# NRF52840-Beacon-V1-4.net
KiCad netlist of a schematic drawn in Altium Designer
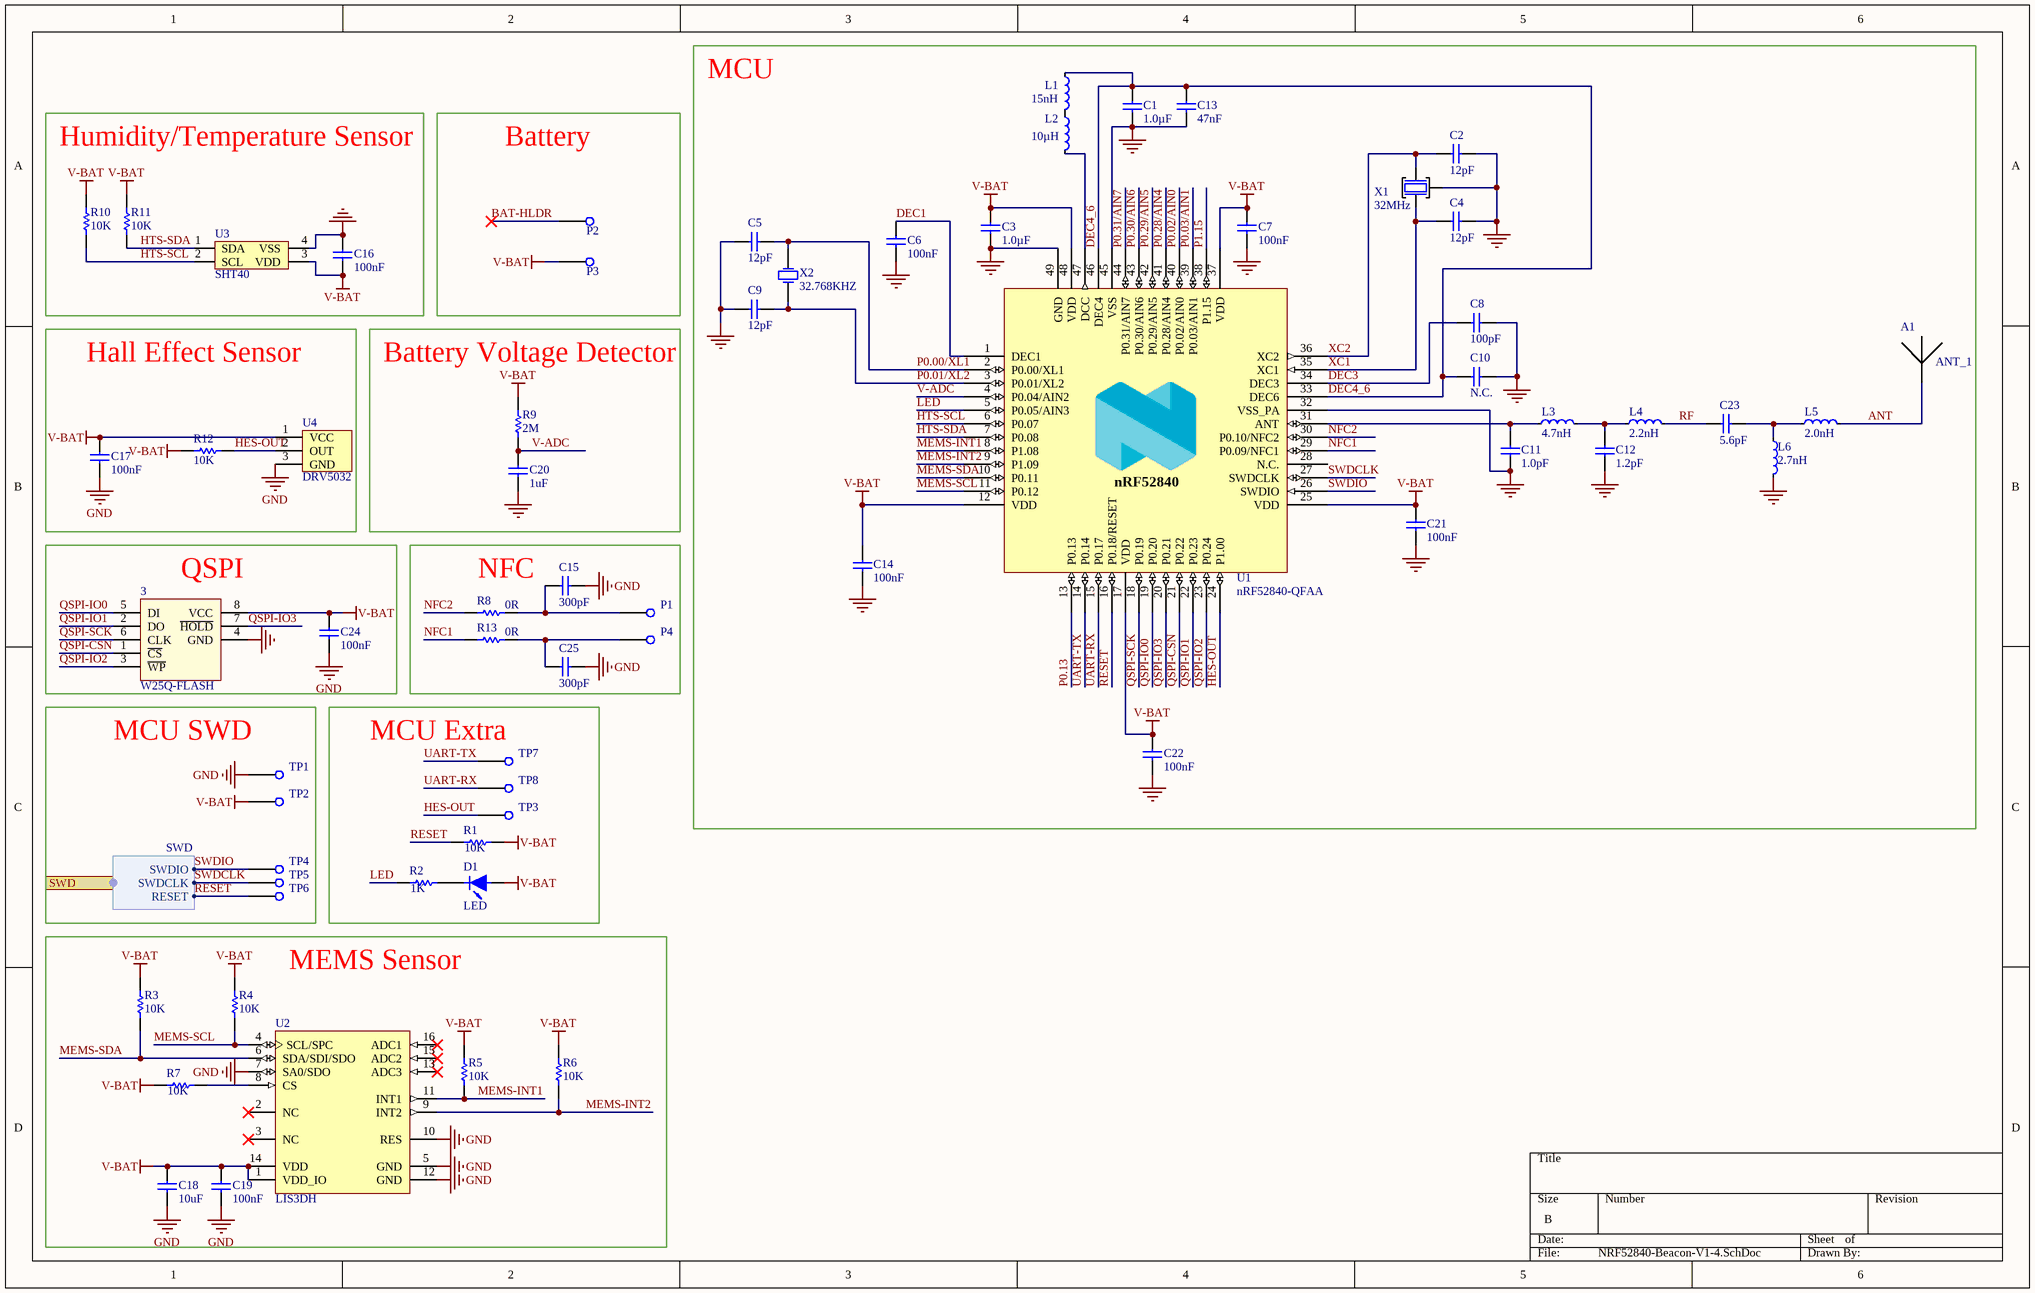
[diagram p0: NRF52840-Beacon-V1-4.SchDoc]

(export (version "E")
  (design (tool "Eeschema 10.0.6"))
  (components
    (comp (ref "3")
      (value "W25Q-FLASH")
      (footprint "SO8W_M")
      (libsource (lib "My Devices") (part "W25Q-FLASH"))
    )
    (comp (ref "A1")
      (value "ANT_1")
      (footprint "ANTENNA_2450AT18B100")
      (fields
        (field (name "PART NUMBER") "Johanson 2450AT18B100")
        (field (name "MANUFACTURER") "Johanson Technology")
        (field (name "MANUFACTURER PART NUMBER") "2450AT18B100")
        (field (name "PUBLISHER") "Nordic Semiconductor")
        (field (name "AUTHOR") "rsk")
      )
      (libsource (lib "My Devices") (part "ANT_1"))
    )
    (comp (ref "C1")
      (value "1.0µF")
      (footprint "CAPC1608N")
      (description "Capacitor, X5R, ±10%")
      (fields (field (name "PART NUMBER") "C0402-1µ0"))
      (libsource (lib "AltiumLib") (part "CAP"))
    )
    (comp (ref "C2")
      (value "12pF")
      (footprint "CAPC1608N")
      (description "Capacitor, NP0, ±2%")
      (fields (field (name "PART NUMBER") "C0201-12p"))
      (libsource (lib "AltiumLib") (part "CAP"))
    )
    (comp (ref "C3")
      (value "1.0µF")
      (footprint "CAPC1608N")
      (description "Capacitor, X5R, ±10%")
      (fields (field (name "PART NUMBER") "C0402-1µ0"))
      (libsource (lib "AltiumLib") (part "CAP"))
    )
    (comp (ref "C4")
      (value "12pF")
      (footprint "CAPC1608N")
      (description "Capacitor, NP0, ±2%")
      (fields (field (name "PART NUMBER") "C0201-12p"))
      (libsource (lib "AltiumLib") (part "CAP"))
    )
    (comp (ref "C5")
      (value "12pF")
      (footprint "CAPC1608N")
      (description "Capacitor, NP0, ±2%")
      (fields (field (name "PART NUMBER") "C0201-12p"))
      (libsource (lib "AltiumLib") (part "CAP"))
    )
    (comp (ref "C6")
      (value "100nF")
      (footprint "CAPC1608N")
      (description "Capacitor, X5R, ±10%")
      (fields (field (name "PART NUMBER") "C0201-100n"))
      (libsource (lib "AltiumLib") (part "CAP"))
    )
    (comp (ref "C7")
      (value "100nF")
      (footprint "CAPC1608N")
      (description "Capacitor, X5R, ±10%")
      (fields (field (name "PART NUMBER") "C0201-100n"))
      (libsource (lib "AltiumLib") (part "CAP"))
    )
    (comp (ref "C8")
      (value "100pF")
      (footprint "CAPC1608N")
      (description "Capacitor, NP0, ±5%")
      (fields (field (name "PART NUMBER") "C0201-100p"))
      (libsource (lib "AltiumLib") (part "CAP"))
    )
    (comp (ref "C9")
      (value "12pF")
      (footprint "CAPC1608N")
      (description "Capacitor, NP0, ±2%")
      (fields (field (name "PART NUMBER") "C0201-12p"))
      (libsource (lib "AltiumLib") (part "CAP"))
    )
    (comp (ref "C10")
      (value "N.C.")
      (footprint "CAPC1608N")
      (description "Not mounted")
      (fields (field (name "PART NUMBER") "C0201-N.C."))
      (libsource (lib "AltiumLib") (part "CAP"))
    )
    (comp (ref "C11")
      (value "1.0pF")
      (footprint "CAPC1608N")
      (description "Capacitor, NP0, ±10%")
      (fields (field (name "PART NUMBER") "C0201-1.0p"))
      (libsource (lib "AltiumLib") (part "CAP"))
    )
    (comp (ref "C12")
      (value "1.2pF")
      (footprint "CAPC1608N")
      (description "Capacitor, NP0, ±10%")
      (fields (field (name "PART NUMBER") "C0201-1.2p"))
      (libsource (lib "AltiumLib") (part "CAP"))
    )
    (comp (ref "C13")
      (value "47nF")
      (footprint "CAPC1608N")
      (description "Capacitor, X5R, ±10%")
      (fields (field (name "PART NUMBER") "C0201-47n"))
      (libsource (lib "AltiumLib") (part "CAP"))
    )
    (comp (ref "C14")
      (value "100nF")
      (footprint "CAPC1608N")
      (description "Capacitor, X5R, ±10%")
      (fields (field (name "PART NUMBER") "C0201-100n"))
      (libsource (lib "AltiumLib") (part "CAP"))
    )
    (comp (ref "C15")
      (value "300pF")
      (footprint "CAPC1608N")
      (description "Capacitor, NP0, ±2%")
      (fields (field (name "PART NUMBER") "C0201-12p"))
      (libsource (lib "AltiumLib") (part "CAP"))
    )
    (comp (ref "C16")
      (value "100nF")
      (footprint "CAPC1608N")
      (description "Capacitor, NP0, ±2%")
      (fields (field (name "PART NUMBER") "C0201-12p"))
      (libsource (lib "AltiumLib") (part "CAP"))
    )
    (comp (ref "C17")
      (value "100nF")
      (footprint "CAPC1608N")
      (description "Capacitor, NP0, ±2%")
      (fields (field (name "PART NUMBER") "C0201-12p"))
      (libsource (lib "AltiumLib") (part "CAP"))
    )
    (comp (ref "C18")
      (value "10uF")
      (footprint "CAPC1608N")
      (description "Capacitor, NP0, ±2%")
      (fields (field (name "PART NUMBER") "C0201-12p"))
      (libsource (lib "AltiumLib") (part "CAP"))
    )
    (comp (ref "C19")
      (value "100nF")
      (footprint "CAPC1608N")
      (description "Capacitor, NP0, ±2%")
      (fields (field (name "PART NUMBER") "C0201-12p"))
      (libsource (lib "AltiumLib") (part "CAP"))
    )
    (comp (ref "C20")
      (value "1uF")
      (footprint "CAPC1608N")
      (description "Capacitor, NP0, ±2%")
      (fields (field (name "PART NUMBER") "C0201-12p"))
      (libsource (lib "AltiumLib") (part "CAP"))
    )
    (comp (ref "C21")
      (value "100nF")
      (footprint "CAPC1608N")
      (description "Capacitor, X5R, ±10%")
      (fields (field (name "PART NUMBER") "C0201-100n"))
      (libsource (lib "AltiumLib") (part "CAP"))
    )
    (comp (ref "C22")
      (value "100nF")
      (footprint "CAPC1608N")
      (description "Capacitor, X5R, ±10%")
      (fields (field (name "PART NUMBER") "C0201-100n"))
      (libsource (lib "AltiumLib") (part "CAP"))
    )
    (comp (ref "C23")
      (value "5.6pF")
      (footprint "CAPC1608N")
      (description "Capacitor, NP0, ±10%")
      (fields (field (name "PART NUMBER") "C0201-1.2p"))
      (libsource (lib "AltiumLib") (part "CAP"))
    )
    (comp (ref "C24")
      (value "100nF")
      (footprint "CAPC1608N")
      (description "Capacitor, NP0, ±2%")
      (fields (field (name "PART NUMBER") "C0201-12p"))
      (libsource (lib "AltiumLib") (part "CAP"))
    )
    (comp (ref "C25")
      (value "300pF")
      (footprint "CAPC1608N")
      (description "Capacitor, NP0, ±2%")
      (fields (field (name "PART NUMBER") "C0201-12p"))
      (libsource (lib "AltiumLib") (part "CAP"))
    )
    (comp (ref "D1")
      (value "LED")
      (footprint "LED_0603")
      (fields (field (name "PUBLISHER") "Altium Limited"))
      (libsource (lib "My Devices") (part "LED"))
    )
    (comp (ref "L1")
      (value "15nH")
      (footprint "INDC1608N")
      (description "High frequency chip inductor ±10%")
      (fields (field (name "PART NUMBER") "L0402-15n"))
      (libsource (lib "AltiumLib") (part "IND"))
    )
    (comp (ref "L2")
      (value "10µH")
      (footprint "INDC1608N")
      (description "Chip inductor, IDC,min = 50 mA, ±20%")
      (fields (field (name "PART NUMBER") "L0603-10µ-TDK"))
      (libsource (lib "AltiumLib") (part "IND"))
    )
    (comp (ref "L3")
      (value "4.7nH")
      (footprint "INDC1608N")
      (description "High frequency chip inductor ±5%")
      (fields (field (name "PART NUMBER") "L0201-4n7"))
      (libsource (lib "AltiumLib") (part "IND"))
    )
    (comp (ref "L4")
      (value "2.2nH")
      (footprint "INDC1608N")
      (description "High frequency chip inductor ±5%")
      (fields (field (name "PART NUMBER") "L0201-2n2"))
      (libsource (lib "AltiumLib") (part "IND"))
    )
    (comp (ref "L5")
      (value "2.0nH")
      (footprint "INDC1608N")
      (description "High frequency chip inductor ±5%")
      (fields (field (name "PART NUMBER") "L0201-4n7"))
      (libsource (lib "AltiumLib") (part "IND"))
    )
    (comp (ref "L6")
      (value "2.7nH")
      (footprint "INDC1608N")
      (description "High frequency chip inductor ±5%")
      (fields (field (name "PART NUMBER") "L0201-4n7"))
      (libsource (lib "AltiumLib") (part "IND"))
    )
    (comp (ref "P1") (value "PIN") (footprint "PIN") (libsource (lib "My Connectors") (part "PIN")))
    (comp (ref "P2") (value "PIN") (footprint "PIN") (libsource (lib "My Connectors") (part "PIN")))
    (comp (ref "P3") (value "PIN") (footprint "PIN") (libsource (lib "My Connectors") (part "PIN")))
    (comp (ref "P4") (value "PIN") (footprint "PIN") (libsource (lib "My Connectors") (part "PIN")))
    (comp (ref "R1") (value "10K") (footprint "RESC1608N") (libsource (lib "My Devices") (part "Resistor")))
    (comp (ref "R2") (value "1K") (footprint "RESC1608N") (libsource (lib "My Devices") (part "Resistor")))
    (comp (ref "R3") (value "10K") (footprint "RESC1608N") (libsource (lib "My Devices") (part "Resistor")))
    (comp (ref "R4") (value "10K") (footprint "RESC1608N") (libsource (lib "My Devices") (part "Resistor")))
    (comp (ref "R5") (value "10K") (footprint "RESC1608N") (libsource (lib "My Devices") (part "Resistor")))
    (comp (ref "R6") (value "10K") (footprint "RESC1608N") (libsource (lib "My Devices") (part "Resistor")))
    (comp (ref "R7") (value "10K") (footprint "RESC1608N") (libsource (lib "My Devices") (part "Resistor")))
    (comp (ref "R8") (value "0R") (footprint "RESC1608N") (libsource (lib "My Devices") (part "Resistor")))
    (comp (ref "R9") (value "2M") (footprint "RESC1608N") (libsource (lib "My Devices") (part "Resistor")))
    (comp (ref "R10") (value "10K") (footprint "RESC1608N") (libsource (lib "My Devices") (part "Resistor")))
    (comp (ref "R11") (value "10K") (footprint "RESC1608N") (libsource (lib "My Devices") (part "Resistor")))
    (comp (ref "R12") (value "10K") (footprint "RESC1608N") (libsource (lib "My Devices") (part "Resistor")))
    (comp (ref "R13") (value "0R") (footprint "RESC1608N") (libsource (lib "My Devices") (part "Resistor")))
    (comp (ref "TP1") (value "PIN") (footprint "PIN") (libsource (lib "My Connectors") (part "PIN")))
    (comp (ref "TP2") (value "PIN") (footprint "PIN") (libsource (lib "My Connectors") (part "PIN")))
    (comp (ref "TP3") (value "PIN") (footprint "PIN") (libsource (lib "My Connectors") (part "PIN")))
    (comp (ref "TP4") (value "PIN") (footprint "PIN") (libsource (lib "My Connectors") (part "PIN")))
    (comp (ref "TP5") (value "PIN") (footprint "PIN") (libsource (lib "My Connectors") (part "PIN")))
    (comp (ref "TP6") (value "PIN") (footprint "PIN") (libsource (lib "My Connectors") (part "PIN")))
    (comp (ref "TP7") (value "PIN") (footprint "PIN") (libsource (lib "My Connectors") (part "PIN")))
    (comp (ref "TP8") (value "PIN") (footprint "PIN") (libsource (lib "My Connectors") (part "PIN")))
    (comp (ref "U1")
      (value "nRF52840-QFAA")
      (footprint "QFN40P600X600X90-48N")
      (description "Multi-protocol Bluetooth Low Energy, IEEE 802.15.4, ANT and 2.4GHz proprietary system-on-chip")
      (libsource (lib "AltiumLib") (part "nRF52840_QFAA"))
    )
    (comp (ref "U2")
      (value "LIS3DH")
      (footprint "LGA-16")
      (fields (field (name "MANUFACTURER") "STMicroelectronics"))
      (libsource (lib "My Devices") (part "LIS3DH"))
    )
    (comp (ref "U3")
      (value "SHT40")
      (footprint "SHT40")
      (description "High-Accuracy, Ultra-Low-Power, 16-bit, Relative Humidity and Temperature Sensor")
      (libsource (lib "My Devices") (part "SHT40"))
    )
    (comp (ref "U4")
      (value "DRV5032")
      (footprint "SOT-23")
      (description "ultra-low-power digital-switch Hall effect sensor")
      (libsource (lib "My Devices") (part "Hall_Effect_Sensor_Switch"))
    )
    (comp (ref "X1")
      (value "32MHz")
      (footprint "CRYSTAL_2016_NT")
      (description "XTAL SMD 2016, 32MHz, Cl=8pF, Total Tol: ±30ppm")
      (fields (field (name "PART NUMBER") "XTAL_SMD2016_32MHz_8pF_General_NT"))
      (libsource (lib "AltiumLib") (part "XTAL_4-pin_NT"))
    )
    (comp (ref "X2")
      (value "32.768KHZ")
      (footprint "CRYSTAL_3215")
      (libsource (lib "My Devices") (part "Crystal_Oscillator_2PIN"))
    )
  )
  (nets
    (net (code "2") (name "/ANT") (class "Default")
      (node (ref "A1") (pin "1") (pinfunction "1_1") (pintype "passive"))
      (node (ref "L5") (pin "2") (pinfunction "2_2") (pintype "passive"))
    )
    (net (code "3") (name "/BAT-HLDR") (class "Default")
      (node (ref "P2") (pin "1") (pinfunction "PIN_1") (pintype "passive+no_connect"))
    )
    (net (code "4") (name "/DEC1") (class "Default")
      (node (ref "C6") (pin "1") (pinfunction "1_1") (pintype "passive"))
      (node (ref "U1") (pin "1") (pinfunction "DEC1_1") (pintype "power_in"))
    )
    (net (code "5") (name "/DEC3") (class "Default")
      (node (ref "C8") (pin "1") (pinfunction "1_1") (pintype "passive"))
      (node (ref "U1") (pin "34") (pinfunction "DEC3_34") (pintype "power_in"))
    )
    (net (code "6") (name "/DEC4_6") (class "Default")
      (node (ref "C1") (pin "2") (pinfunction "2_2") (pintype "passive"))
      (node (ref "C10") (pin "2") (pinfunction "2_2") (pintype "passive"))
      (node (ref "C13") (pin "1") (pinfunction "1_1") (pintype "passive"))
      (node (ref "L1") (pin "1") (pinfunction "1_1") (pintype "passive"))
      (node (ref "U1") (pin "33") (pinfunction "DEC6_33") (pintype "power_in"))
      (node (ref "U1") (pin "46") (pinfunction "DEC4_46") (pintype "power_in"))
    )
    (net (code "7") (name "/HES-OUT") (class "Default")
      (node (ref "R12") (pin "2") (pinfunction "2_2") (pintype "passive"))
      (node (ref "TP3") (pin "1") (pinfunction "PIN_1") (pintype "passive"))
      (node (ref "U1") (pin "24") (pinfunction "P1.00_24") (pintype "bidirectional"))
      (node (ref "U4") (pin "2") (pinfunction "OUT_2") (pintype "passive"))
    )
    (net (code "8") (name "/HTS-SCL") (class "Default")
      (node (ref "R10") (pin "2") (pinfunction "2_2") (pintype "passive"))
      (node (ref "U1") (pin "6") (pinfunction "P0.07_6") (pintype "bidirectional"))
      (node (ref "U3") (pin "2") (pinfunction "SCL_2") (pintype "passive"))
    )
    (net (code "9") (name "/HTS-SDA") (class "Default")
      (node (ref "R11") (pin "2") (pinfunction "2_2") (pintype "passive"))
      (node (ref "U1") (pin "7") (pinfunction "P0.08_7") (pintype "bidirectional"))
      (node (ref "U3") (pin "1") (pinfunction "SDA_1") (pintype "passive"))
    )
    (net (code "10") (name "/LED") (class "Default")
      (node (ref "R2") (pin "1") (pinfunction "1_1") (pintype "passive"))
      (node (ref "U1") (pin "5") (pinfunction "P0.05/AIN3_5") (pintype "bidirectional"))
    )
    (net (code "11") (name "/MEMS-INT1") (class "Default")
      (node (ref "R5") (pin "2") (pinfunction "2_2") (pintype "passive"))
      (node (ref "U1") (pin "8") (pinfunction "P1.08_8") (pintype "bidirectional"))
      (node (ref "U2") (pin "11") (pinfunction "INT1_11") (pintype "output"))
    )
    (net (code "12") (name "/MEMS-INT2") (class "Default")
      (node (ref "R6") (pin "2") (pinfunction "2_2") (pintype "passive"))
      (node (ref "U1") (pin "9") (pinfunction "P1.09_9") (pintype "bidirectional"))
      (node (ref "U2") (pin "9") (pinfunction "INT2_9") (pintype "output"))
    )
    (net (code "13") (name "/MEMS-SCL") (class "Default")
      (node (ref "R4") (pin "2") (pinfunction "2_2") (pintype "passive"))
      (node (ref "U1") (pin "11") (pinfunction "P0.12_11") (pintype "bidirectional"))
      (node (ref "U2") (pin "4") (pinfunction "SCL/SPC_4") (pintype "bidirectional"))
    )
    (net (code "14") (name "/MEMS-SDA") (class "Default")
      (node (ref "R3") (pin "2") (pinfunction "2_2") (pintype "passive"))
      (node (ref "U1") (pin "10") (pinfunction "P0.11_10") (pintype "bidirectional"))
      (node (ref "U2") (pin "6") (pinfunction "SDA/SDI/SDO_6") (pintype "bidirectional"))
    )
    (net (code "15") (name "/NFC1") (class "Default")
      (node (ref "R13") (pin "2") (pinfunction "2_2") (pintype "passive"))
      (node (ref "U1") (pin "29") (pinfunction "P0.09/NFC1_29") (pintype "bidirectional"))
    )
    (net (code "16") (name "/NFC2") (class "Default")
      (node (ref "R8") (pin "2") (pinfunction "2_2") (pintype "passive"))
      (node (ref "U1") (pin "30") (pinfunction "P0.10/NFC2_30") (pintype "bidirectional"))
    )
    (net (code "17") (name "/P0.00{slash}XL1") (class "Default")
      (node (ref "C5") (pin "1") (pinfunction "1_1") (pintype "passive"))
      (node (ref "U1") (pin "2") (pinfunction "P0.00/XL1_2") (pintype "bidirectional"))
      (node (ref "X2") (pin "2") (pinfunction "OSC2_2") (pintype "passive"))
    )
    (net (code "18") (name "/P0.01{slash}XL2") (class "Default")
      (node (ref "C9") (pin "1") (pinfunction "1_1") (pintype "passive"))
      (node (ref "U1") (pin "3") (pinfunction "P0.01/XL2_3") (pintype "bidirectional"))
      (node (ref "X2") (pin "1") (pinfunction "OSC1_1") (pintype "passive"))
    )
    (net (code "19") (name "/P0.02{slash}AIN0") (class "Default")
      (node (ref "U1") (pin "40") (pinfunction "P0.02/AIN0_40") (pintype "bidirectional"))
    )
    (net (code "20") (name "/P0.03{slash}AIN1") (class "Default")
      (node (ref "U1") (pin "39") (pinfunction "P0.03/AIN1_39") (pintype "bidirectional"))
    )
    (net (code "21") (name "/P0.13") (class "Default")
      (node (ref "U1") (pin "13") (pinfunction "P0.13_13") (pintype "bidirectional"))
    )
    (net (code "22") (name "/P0.28{slash}AIN4") (class "Default")
      (node (ref "U1") (pin "41") (pinfunction "P0.28/AIN4_41") (pintype "bidirectional"))
    )
    (net (code "23") (name "/P0.29{slash}AIN5") (class "Default")
      (node (ref "U1") (pin "42") (pinfunction "P0.29/AIN5_42") (pintype "bidirectional"))
    )
    (net (code "24") (name "/P0.30{slash}AIN6") (class "Default")
      (node (ref "U1") (pin "43") (pinfunction "P0.30/AIN6_43") (pintype "bidirectional"))
    )
    (net (code "25") (name "/P0.31{slash}AIN7") (class "Default")
      (node (ref "U1") (pin "44") (pinfunction "P0.31/AIN7_44") (pintype "bidirectional"))
    )
    (net (code "26") (name "/P1.15") (class "Default")
      (node (ref "U1") (pin "38") (pinfunction "P1.15_38") (pintype "bidirectional"))
    )
    (net (code "27") (name "/QSPI-CSN") (class "Default")
      (node (ref "3") (pin "1") (pinfunction "~{CS}_1") (pintype "passive"))
      (node (ref "U1") (pin "21") (pinfunction "P0.22_21") (pintype "bidirectional"))
    )
    (net (code "28") (name "/QSPI-IO0") (class "Default")
      (node (ref "3") (pin "5") (pinfunction "DI_5") (pintype "passive"))
      (node (ref "U1") (pin "19") (pinfunction "P0.20_19") (pintype "bidirectional"))
    )
    (net (code "29") (name "/QSPI-IO1") (class "Default")
      (node (ref "3") (pin "2") (pinfunction "DO_2") (pintype "passive"))
      (node (ref "U1") (pin "22") (pinfunction "P0.23_22") (pintype "bidirectional"))
    )
    (net (code "30") (name "/QSPI-IO2") (class "Default")
      (node (ref "3") (pin "3") (pinfunction "~{WP}_3") (pintype "passive"))
      (node (ref "U1") (pin "23") (pinfunction "P0.24_23") (pintype "bidirectional"))
    )
    (net (code "31") (name "/QSPI-IO3") (class "Default")
      (node (ref "3") (pin "7") (pinfunction "~{HOLD}_7") (pintype "passive"))
      (node (ref "U1") (pin "20") (pinfunction "P0.21_20") (pintype "bidirectional"))
    )
    (net (code "32") (name "/QSPI-SCK") (class "Default")
      (node (ref "3") (pin "6") (pinfunction "CLK_6") (pintype "passive"))
      (node (ref "U1") (pin "18") (pinfunction "P0.19_18") (pintype "bidirectional"))
    )
    (net (code "33") (name "/RESET") (class "Default")
      (node (ref "R1") (pin "1") (pinfunction "1_1") (pintype "passive"))
      (node (ref "TP6") (pin "1") (pinfunction "PIN_1") (pintype "passive"))
      (node (ref "U1") (pin "16") (pinfunction "P0.18/RESET_16") (pintype "bidirectional"))
    )
    (net (code "34") (name "/RF") (class "Default")
      (node (ref "C23") (pin "2") (pinfunction "2_2") (pintype "passive"))
      (node (ref "L4") (pin "2") (pinfunction "2_2") (pintype "passive"))
    )
    (net (code "35") (name "/SWDCLK") (class "Default")
      (node (ref "TP5") (pin "1") (pinfunction "PIN_1") (pintype "passive"))
      (node (ref "U1") (pin "27") (pinfunction "SWDCLK_27") (pintype "bidirectional"))
    )
    (net (code "36") (name "/SWDIO") (class "Default")
      (node (ref "TP4") (pin "1") (pinfunction "PIN_1") (pintype "passive"))
      (node (ref "U1") (pin "26") (pinfunction "SWDIO_26") (pintype "input"))
    )
    (net (code "37") (name "/UART-RX") (class "Default")
      (node (ref "TP8") (pin "1") (pinfunction "PIN_1") (pintype "passive"))
      (node (ref "U1") (pin "15") (pinfunction "P0.17_15") (pintype "bidirectional"))
    )
    (net (code "38") (name "/UART-TX") (class "Default")
      (node (ref "TP7") (pin "1") (pinfunction "PIN_1") (pintype "passive"))
      (node (ref "U1") (pin "14") (pinfunction "P0.14_14") (pintype "bidirectional"))
    )
    (net (code "39") (name "/V-ADC") (class "Default")
      (node (ref "C20") (pin "1") (pinfunction "1_1") (pintype "passive"))
      (node (ref "R9") (pin "1") (pinfunction "1_1") (pintype "passive"))
      (node (ref "U1") (pin "4") (pinfunction "P0.04/AIN2_4") (pintype "bidirectional"))
    )
    (net (code "40") (name "/XC1") (class "Default")
      (node (ref "C4") (pin "1") (pinfunction "1_1") (pintype "passive"))
      (node (ref "U1") (pin "35") (pinfunction "XC1_35") (pintype "input"))
      (node (ref "X1") (pin "1") (pinfunction "IN_1") (pintype "passive"))
    )
    (net (code "41") (name "/XC2") (class "Default")
      (node (ref "C2") (pin "1") (pinfunction "1_1") (pintype "passive"))
      (node (ref "U1") (pin "36") (pinfunction "XC2_36") (pintype "output"))
      (node (ref "X1") (pin "3") (pinfunction "OUT_3") (pintype "passive"))
    )
    (net (code "43") (name "GND") (class "Default")
      (node (ref "3") (pin "4") (pinfunction "GND_4") (pintype "passive"))
      (node (ref "C1") (pin "1") (pinfunction "1_1") (pintype "passive"))
      (node (ref "C10") (pin "1") (pinfunction "1_1") (pintype "passive"))
      (node (ref "C11") (pin "1") (pinfunction "1_1") (pintype "passive"))
      (node (ref "C12") (pin "1") (pinfunction "1_1") (pintype "passive"))
      (node (ref "C13") (pin "2") (pinfunction "2_2") (pintype "passive"))
      (node (ref "C14") (pin "2") (pinfunction "2_2") (pintype "passive"))
      (node (ref "C15") (pin "2") (pinfunction "2_2") (pintype "passive"))
      (node (ref "C16") (pin "1") (pinfunction "1_1") (pintype "passive"))
      (node (ref "C17") (pin "2") (pinfunction "2_2") (pintype "passive"))
      (node (ref "C18") (pin "2") (pinfunction "2_2") (pintype "passive"))
      (node (ref "C19") (pin "2") (pinfunction "2_2") (pintype "passive"))
      (node (ref "C2") (pin "2") (pinfunction "2_2") (pintype "passive"))
      (node (ref "C20") (pin "2") (pinfunction "2_2") (pintype "passive"))
      (node (ref "C21") (pin "2") (pinfunction "2_2") (pintype "passive"))
      (node (ref "C22") (pin "2") (pinfunction "2_2") (pintype "passive"))
      (node (ref "C24") (pin "2") (pinfunction "2_2") (pintype "passive"))
      (node (ref "C25") (pin "2") (pinfunction "2_2") (pintype "passive"))
      (node (ref "C3") (pin "2") (pinfunction "2_2") (pintype "passive"))
      (node (ref "C4") (pin "2") (pinfunction "2_2") (pintype "passive"))
      (node (ref "C5") (pin "2") (pinfunction "2_2") (pintype "passive"))
      (node (ref "C6") (pin "2") (pinfunction "2_2") (pintype "passive"))
      (node (ref "C7") (pin "2") (pinfunction "2_2") (pintype "passive"))
      (node (ref "C8") (pin "2") (pinfunction "2_2") (pintype "passive"))
      (node (ref "C9") (pin "2") (pinfunction "2_2") (pintype "passive"))
      (node (ref "L6") (pin "2") (pinfunction "2_2") (pintype "passive"))
      (node (ref "TP1") (pin "1") (pinfunction "PIN_1") (pintype "passive"))
      (node (ref "U1") (pin "32") (pinfunction "VSS_PA_32") (pintype "power_in"))
      (node (ref "U1") (pin "45") (pinfunction "VSS_45") (pintype "power_in"))
      (node (ref "U1") (pin "49") (pinfunction "GND_49") (pintype "power_in"))
      (node (ref "U2") (pin "10") (pinfunction "RES_10") (pintype "power_in"))
      (node (ref "U2") (pin "12") (pinfunction "GND_12") (pintype "power_in"))
      (node (ref "U2") (pin "5") (pinfunction "GND_5") (pintype "power_in"))
      (node (ref "U2") (pin "7") (pinfunction "SA0/SDO_7") (pintype "bidirectional"))
      (node (ref "U3") (pin "4") (pinfunction "VSS_4") (pintype "passive"))
      (node (ref "U4") (pin "3") (pinfunction "GND_3") (pintype "passive"))
      (node (ref "X1") (pin "2") (pinfunction "GND_2") (pintype "passive"))
    )
    (net (code "44") (name "Net-(C12-Pad2)") (class "Default")
      (node (ref "C12") (pin "2") (pinfunction "2_2") (pintype "passive"))
      (node (ref "L3") (pin "2") (pinfunction "2_2") (pintype "passive"))
      (node (ref "L4") (pin "1") (pinfunction "1_1") (pintype "passive"))
    )
    (net (code "45") (name "Net-(C23-Pad1)") (class "Default")
      (node (ref "C23") (pin "1") (pinfunction "1_1") (pintype "passive"))
      (node (ref "L5") (pin "1") (pinfunction "1_1") (pintype "passive"))
      (node (ref "L6") (pin "1") (pinfunction "1_1") (pintype "passive"))
    )
    (net (code "46") (name "Net-(D1-K)") (class "Default")
      (node (ref "D1") (pin "2") (pinfunction "K_2") (pintype "passive"))
      (node (ref "R2") (pin "2") (pinfunction "2_2") (pintype "passive"))
    )
    (net (code "47") (name "Net-(L1-Pad2)") (class "Default")
      (node (ref "L1") (pin "2") (pinfunction "2_2") (pintype "passive"))
      (node (ref "L2") (pin "1") (pinfunction "1_1") (pintype "passive"))
    )
    (net (code "48") (name "Net-(P1-PIN)") (class "Default")
      (node (ref "C15") (pin "1") (pinfunction "1_1") (pintype "passive"))
      (node (ref "P1") (pin "1") (pinfunction "PIN_1") (pintype "passive"))
      (node (ref "R8") (pin "1") (pinfunction "1_1") (pintype "passive"))
    )
    (net (code "49") (name "Net-(P4-PIN)") (class "Default")
      (node (ref "C25") (pin "1") (pinfunction "1_1") (pintype "passive"))
      (node (ref "P4") (pin "1") (pinfunction "PIN_1") (pintype "passive"))
      (node (ref "R13") (pin "1") (pinfunction "1_1") (pintype "passive"))
    )
    (net (code "50") (name "Net-(U1-ANT)") (class "Default")
      (node (ref "C11") (pin "2") (pinfunction "2_2") (pintype "passive"))
      (node (ref "L3") (pin "1") (pinfunction "1_1") (pintype "passive"))
      (node (ref "U1") (pin "31") (pinfunction "ANT_31") (pintype "bidirectional"))
    )
    (net (code "51") (name "Net-(U1-DCC)") (class "Default")
      (node (ref "L2") (pin "2") (pinfunction "2_2") (pintype "passive"))
      (node (ref "U1") (pin "47") (pinfunction "DCC_47") (pintype "output"))
    )
    (net (code "52") (name "Net-(U2-CS)") (class "Default")
      (node (ref "R7") (pin "2") (pinfunction "2_2") (pintype "passive"))
      (node (ref "U2") (pin "8") (pinfunction "CS_8") (pintype "input"))
    )
    (net (code "53") (name "V-BAT") (class "Default")
      (node (ref "3") (pin "8") (pinfunction "VCC_8") (pintype "passive"))
      (node (ref "C14") (pin "1") (pinfunction "1_1") (pintype "passive"))
      (node (ref "C16") (pin "2") (pinfunction "2_2") (pintype "passive"))
      (node (ref "C17") (pin "1") (pinfunction "1_1") (pintype "passive"))
      (node (ref "C18") (pin "1") (pinfunction "1_1") (pintype "passive"))
      (node (ref "C19") (pin "1") (pinfunction "1_1") (pintype "passive"))
      (node (ref "C21") (pin "1") (pinfunction "1_1") (pintype "passive"))
      (node (ref "C22") (pin "1") (pinfunction "1_1") (pintype "passive"))
      (node (ref "C24") (pin "1") (pinfunction "1_1") (pintype "passive"))
      (node (ref "C3") (pin "1") (pinfunction "1_1") (pintype "passive"))
      (node (ref "C7") (pin "1") (pinfunction "1_1") (pintype "passive"))
      (node (ref "D1") (pin "1") (pinfunction "A_1") (pintype "passive"))
      (node (ref "P3") (pin "1") (pinfunction "PIN_1") (pintype "passive"))
      (node (ref "R1") (pin "2") (pinfunction "2_2") (pintype "passive"))
      (node (ref "R10") (pin "1") (pinfunction "1_1") (pintype "passive"))
      (node (ref "R11") (pin "1") (pinfunction "1_1") (pintype "passive"))
      (node (ref "R12") (pin "1") (pinfunction "1_1") (pintype "passive"))
      (node (ref "R3") (pin "1") (pinfunction "1_1") (pintype "passive"))
      (node (ref "R4") (pin "1") (pinfunction "1_1") (pintype "passive"))
      (node (ref "R5") (pin "1") (pinfunction "1_1") (pintype "passive"))
      (node (ref "R6") (pin "1") (pinfunction "1_1") (pintype "passive"))
      (node (ref "R7") (pin "1") (pinfunction "1_1") (pintype "passive"))
      (node (ref "R9") (pin "2") (pinfunction "2_2") (pintype "passive"))
      (node (ref "TP2") (pin "1") (pinfunction "PIN_1") (pintype "passive"))
      (node (ref "U1") (pin "12") (pinfunction "VDD_12") (pintype "power_in"))
      (node (ref "U1") (pin "17") (pinfunction "VDD_17") (pintype "power_in"))
      (node (ref "U1") (pin "25") (pinfunction "VDD_25") (pintype "power_in"))
      (node (ref "U1") (pin "37") (pinfunction "VDD_37") (pintype "power_in"))
      (node (ref "U1") (pin "48") (pinfunction "VDD_48") (pintype "power_in"))
      (node (ref "U2") (pin "1") (pinfunction "VDD_IO_1") (pintype "power_in"))
      (node (ref "U2") (pin "14") (pinfunction "VDD_14") (pintype "power_in"))
      (node (ref "U3") (pin "3") (pinfunction "VDD_3") (pintype "passive"))
      (node (ref "U4") (pin "1") (pinfunction "VCC_1") (pintype "passive"))
    )
    (net (code "54") (name "unconnected-(U1-N.C.-Pad28)") (class "Default")
      (node (ref "U1") (pin "28") (pinfunction "N.C._28") (pintype "passive"))
    )
    (net (code "55") (name "unconnected-(U2-ADC1-Pad16)") (class "Default")
      (node (ref "U2") (pin "16") (pinfunction "ADC1_16") (pintype "input+no_connect"))
    )
    (net (code "56") (name "unconnected-(U2-ADC2-Pad15)") (class "Default")
      (node (ref "U2") (pin "15") (pinfunction "ADC2_15") (pintype "input+no_connect"))
    )
    (net (code "57") (name "unconnected-(U2-ADC3-Pad13)") (class "Default")
      (node (ref "U2") (pin "13") (pinfunction "ADC3_13") (pintype "input+no_connect"))
    )
    (net (code "58") (name "unconnected-(U2-NC-Pad2)") (class "Default")
      (node (ref "U2") (pin "2") (pinfunction "NC_2") (pintype "passive+no_connect"))
    )
    (net (code "59") (name "unconnected-(U2-NC-Pad3)") (class "Default")
      (node (ref "U2") (pin "3") (pinfunction "NC_3") (pintype "passive+no_connect"))
    )
  )
)
